# multisonar_shield.net
KiCad netlist of a schematic drawn in EAGLE
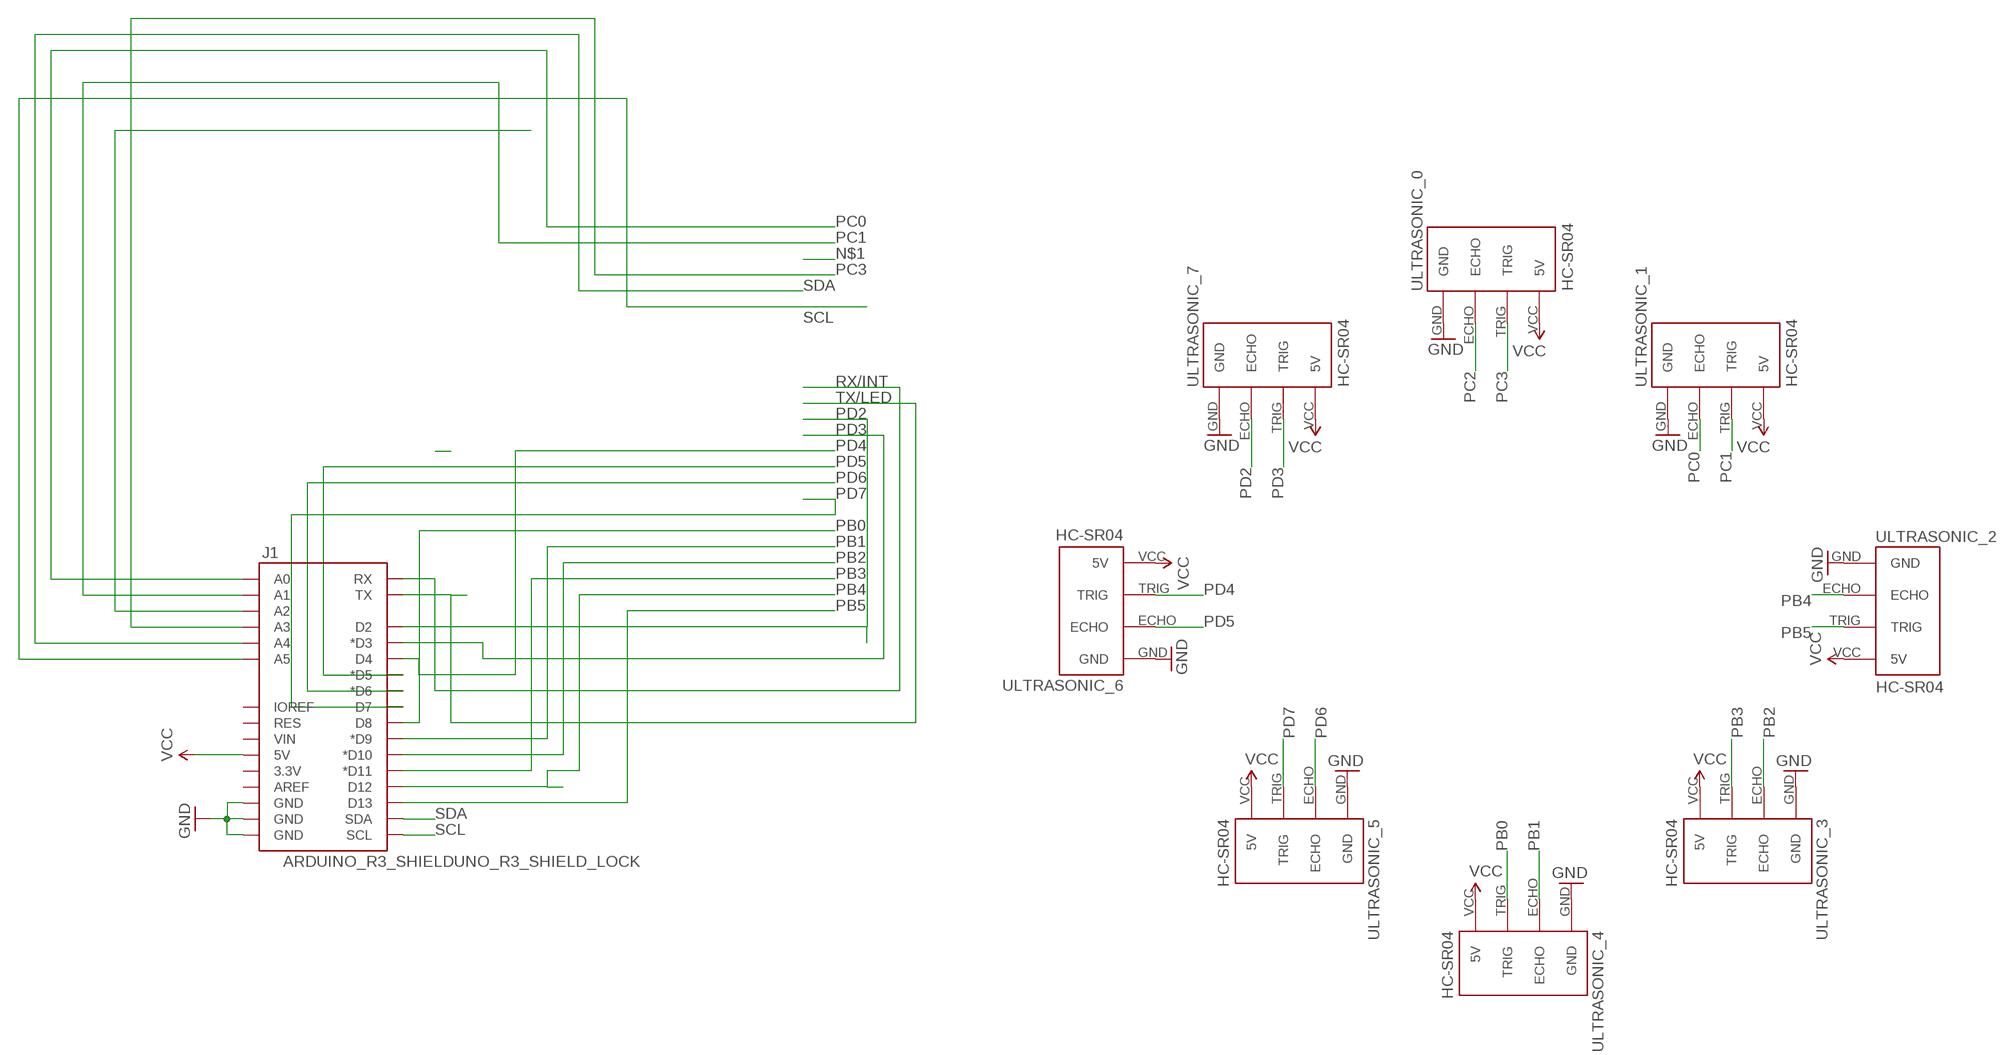
[diagram p0: schematic, sheet 1]

(export (version "E")
  (design (tool "Eeschema 10.0.6"))
  (components
    (comp (ref "J1")
      (value "ARDUINO_R3_SHIELDUNO_R3_SHIELD_LOCK")
      (footprint "eagle-import:UNO_R3_SHIELD_LOCK")
      (libsource (lib "eagle-import") (part "ARDUINO_R3_SHIELDUNO_R3_SHIELD_LOCK"))
    )
    (comp (ref "ULTRASONIC_0")
      (value "HC-SR04")
      (footprint "eagle-import:HC-SR04_FOOTPRINT")
      (libsource (lib "eagle-import") (part "HC-SR04"))
    )
    (comp (ref "ULTRASONIC_1")
      (value "HC-SR04")
      (footprint "eagle-import:HC-SR04_FOOTPRINT")
      (libsource (lib "eagle-import") (part "HC-SR04"))
    )
    (comp (ref "ULTRASONIC_2")
      (value "HC-SR04")
      (footprint "eagle-import:HC-SR04_FOOTPRINT")
      (libsource (lib "eagle-import") (part "HC-SR04"))
    )
    (comp (ref "ULTRASONIC_3")
      (value "HC-SR04")
      (footprint "eagle-import:HC-SR04_FOOTPRINT")
      (libsource (lib "eagle-import") (part "HC-SR04"))
    )
    (comp (ref "ULTRASONIC_4")
      (value "HC-SR04")
      (footprint "eagle-import:HC-SR04_FOOTPRINT")
      (libsource (lib "eagle-import") (part "HC-SR04"))
    )
    (comp (ref "ULTRASONIC_5")
      (value "HC-SR04")
      (footprint "eagle-import:HC-SR04_FOOTPRINT")
      (libsource (lib "eagle-import") (part "HC-SR04"))
    )
    (comp (ref "ULTRASONIC_6")
      (value "HC-SR04")
      (footprint "eagle-import:HC-SR04_FOOTPRINT")
      (libsource (lib "eagle-import") (part "HC-SR04"))
    )
    (comp (ref "ULTRASONIC_7")
      (value "HC-SR04")
      (footprint "eagle-import:HC-SR04_FOOTPRINT")
      (libsource (lib "eagle-import") (part "HC-SR04"))
    )
  )
  (nets
    (net (code "2") (name "/PB0") (class "Default")
      (node (ref "J1") (pin "D8") (pinfunction "D8_D8") (pintype "bidirectional"))
      (node (ref "ULTRASONIC_4") (pin "TRIG") (pinfunction "TRIG_TRIG") (pintype "bidirectional"))
    )
    (net (code "3") (name "/PB1") (class "Default")
      (node (ref "J1") (pin "D9") (pinfunction "*D9_D9") (pintype "bidirectional"))
      (node (ref "ULTRASONIC_4") (pin "ECHO") (pinfunction "ECHO_ECHO") (pintype "bidirectional"))
    )
    (net (code "4") (name "/PB2") (class "Default")
      (node (ref "J1") (pin "D10") (pinfunction "*D10_D10") (pintype "bidirectional"))
      (node (ref "ULTRASONIC_3") (pin "ECHO") (pinfunction "ECHO_ECHO") (pintype "bidirectional"))
    )
    (net (code "5") (name "/PB3") (class "Default")
      (node (ref "J1") (pin "D11") (pinfunction "*D11_D11") (pintype "bidirectional"))
      (node (ref "ULTRASONIC_3") (pin "TRIG") (pinfunction "TRIG_TRIG") (pintype "bidirectional"))
    )
    (net (code "6") (name "/PB4") (class "Default")
      (node (ref "J1") (pin "D12") (pinfunction "D12_D12") (pintype "bidirectional"))
      (node (ref "ULTRASONIC_2") (pin "ECHO") (pinfunction "ECHO_ECHO") (pintype "bidirectional"))
    )
    (net (code "7") (name "/PB5") (class "Default")
      (node (ref "J1") (pin "D13") (pinfunction "D13_D13") (pintype "bidirectional"))
      (node (ref "ULTRASONIC_2") (pin "TRIG") (pinfunction "TRIG_TRIG") (pintype "bidirectional"))
    )
    (net (code "8") (name "/PC0") (class "Default")
      (node (ref "J1") (pin "A0") (pinfunction "A0_A0") (pintype "bidirectional"))
      (node (ref "ULTRASONIC_1") (pin "ECHO") (pinfunction "ECHO_ECHO") (pintype "bidirectional"))
    )
    (net (code "9") (name "/PC1") (class "Default")
      (node (ref "J1") (pin "A1") (pinfunction "A1_A1") (pintype "bidirectional"))
      (node (ref "ULTRASONIC_1") (pin "TRIG") (pinfunction "TRIG_TRIG") (pintype "bidirectional"))
    )
    (net (code "10") (name "/PC2") (class "Default")
      (node (ref "J1") (pin "A2") (pinfunction "A2_A2") (pintype "bidirectional"))
      (node (ref "ULTRASONIC_0") (pin "ECHO") (pinfunction "ECHO_ECHO") (pintype "bidirectional"))
    )
    (net (code "11") (name "/PC3") (class "Default")
      (node (ref "J1") (pin "A3") (pinfunction "A3_A3") (pintype "bidirectional"))
      (node (ref "ULTRASONIC_0") (pin "TRIG") (pinfunction "TRIG_TRIG") (pintype "bidirectional"))
    )
    (net (code "12") (name "/PD2") (class "Default")
      (node (ref "J1") (pin "D2") (pinfunction "D2_D2") (pintype "bidirectional"))
      (node (ref "ULTRASONIC_7") (pin "ECHO") (pinfunction "ECHO_ECHO") (pintype "bidirectional"))
    )
    (net (code "13") (name "/PD3") (class "Default")
      (node (ref "J1") (pin "D3") (pinfunction "*D3_D3") (pintype "bidirectional"))
      (node (ref "ULTRASONIC_7") (pin "TRIG") (pinfunction "TRIG_TRIG") (pintype "bidirectional"))
    )
    (net (code "14") (name "/PD4") (class "Default")
      (node (ref "J1") (pin "D4") (pinfunction "D4_D4") (pintype "bidirectional"))
      (node (ref "ULTRASONIC_6") (pin "TRIG") (pinfunction "TRIG_TRIG") (pintype "bidirectional"))
    )
    (net (code "15") (name "/PD5") (class "Default")
      (node (ref "J1") (pin "D5") (pinfunction "*D5_D5") (pintype "bidirectional"))
      (node (ref "ULTRASONIC_6") (pin "ECHO") (pinfunction "ECHO_ECHO") (pintype "bidirectional"))
    )
    (net (code "16") (name "/PD6") (class "Default")
      (node (ref "J1") (pin "D6") (pinfunction "*D6_D6") (pintype "bidirectional"))
      (node (ref "ULTRASONIC_5") (pin "ECHO") (pinfunction "ECHO_ECHO") (pintype "bidirectional"))
    )
    (net (code "17") (name "/PD7") (class "Default")
      (node (ref "J1") (pin "D7") (pinfunction "D7_D7") (pintype "bidirectional"))
      (node (ref "ULTRASONIC_5") (pin "TRIG") (pinfunction "TRIG_TRIG") (pintype "bidirectional"))
    )
    (net (code "18") (name "/RX{slash}INT") (class "Default")
      (node (ref "J1") (pin "RX") (pinfunction "RX_RX") (pintype "bidirectional"))
    )
    (net (code "19") (name "/SCL") (class "Default")
      (node (ref "J1") (pin "A5") (pinfunction "A5_A5") (pintype "bidirectional"))
      (node (ref "J1") (pin "SCL") (pinfunction "SCL_SCL") (pintype "bidirectional"))
    )
    (net (code "20") (name "/SDA") (class "Default")
      (node (ref "J1") (pin "A4") (pinfunction "A4_A4") (pintype "bidirectional"))
      (node (ref "J1") (pin "SDA") (pinfunction "SDA_SDA") (pintype "bidirectional"))
    )
    (net (code "21") (name "/TX{slash}LED") (class "Default")
      (node (ref "J1") (pin "TX") (pinfunction "TX_TX") (pintype "bidirectional"))
    )
    (net (code "22") (name "GND") (class "Default")
      (node (ref "J1") (pin "GND@0") (pinfunction "GND_GND@0") (pintype "bidirectional"))
      (node (ref "J1") (pin "GND@1") (pinfunction "GND_GND@1") (pintype "bidirectional"))
      (node (ref "J1") (pin "GND@2") (pinfunction "GND_GND@2") (pintype "bidirectional"))
      (node (ref "ULTRASONIC_0") (pin "GND") (pinfunction "GND_GND") (pintype "bidirectional"))
      (node (ref "ULTRASONIC_1") (pin "GND") (pinfunction "GND_GND") (pintype "bidirectional"))
      (node (ref "ULTRASONIC_2") (pin "GND") (pinfunction "GND_GND") (pintype "bidirectional"))
      (node (ref "ULTRASONIC_3") (pin "GND") (pinfunction "GND_GND") (pintype "bidirectional"))
      (node (ref "ULTRASONIC_4") (pin "GND") (pinfunction "GND_GND") (pintype "bidirectional"))
      (node (ref "ULTRASONIC_5") (pin "GND") (pinfunction "GND_GND") (pintype "bidirectional"))
      (node (ref "ULTRASONIC_6") (pin "GND") (pinfunction "GND_GND") (pintype "bidirectional"))
      (node (ref "ULTRASONIC_7") (pin "GND") (pinfunction "GND_GND") (pintype "bidirectional"))
    )
    (net (code "23") (name "VCC") (class "Default")
      (node (ref "J1") (pin "5V") (pinfunction "5V_5V") (pintype "bidirectional"))
      (node (ref "ULTRASONIC_0") (pin "VCC") (pinfunction "5V_VCC") (pintype "bidirectional"))
      (node (ref "ULTRASONIC_1") (pin "VCC") (pinfunction "5V_VCC") (pintype "bidirectional"))
      (node (ref "ULTRASONIC_2") (pin "VCC") (pinfunction "5V_VCC") (pintype "bidirectional"))
      (node (ref "ULTRASONIC_3") (pin "VCC") (pinfunction "5V_VCC") (pintype "bidirectional"))
      (node (ref "ULTRASONIC_4") (pin "VCC") (pinfunction "5V_VCC") (pintype "bidirectional"))
      (node (ref "ULTRASONIC_5") (pin "VCC") (pinfunction "5V_VCC") (pintype "bidirectional"))
      (node (ref "ULTRASONIC_6") (pin "VCC") (pinfunction "5V_VCC") (pintype "bidirectional"))
      (node (ref "ULTRASONIC_7") (pin "VCC") (pinfunction "5V_VCC") (pintype "bidirectional"))
    )
    (net (code "24") (name "unconnected-(J1-Pad3.3V)") (class "Default")
      (node (ref "J1") (pin "3.3V") (pinfunction "3.3V_3.3V") (pintype "bidirectional"))
    )
    (net (code "25") (name "unconnected-(J1-PadAREF)") (class "Default")
      (node (ref "J1") (pin "AREF") (pinfunction "AREF_AREF") (pintype "bidirectional"))
    )
    (net (code "26") (name "unconnected-(J1-PadIOREF)") (class "Default")
      (node (ref "J1") (pin "IOREF") (pinfunction "IOREF_IOREF") (pintype "bidirectional"))
    )
    (net (code "27") (name "unconnected-(J1-PadRES)") (class "Default")
      (node (ref "J1") (pin "RES") (pinfunction "RES_RES") (pintype "bidirectional"))
    )
    (net (code "28") (name "unconnected-(J1-PadVIN)") (class "Default")
      (node (ref "J1") (pin "VIN") (pinfunction "VIN_VIN") (pintype "bidirectional"))
    )
  )
)
